# Shakey.net
KiCad netlist of a schematic drawn in EAGLE
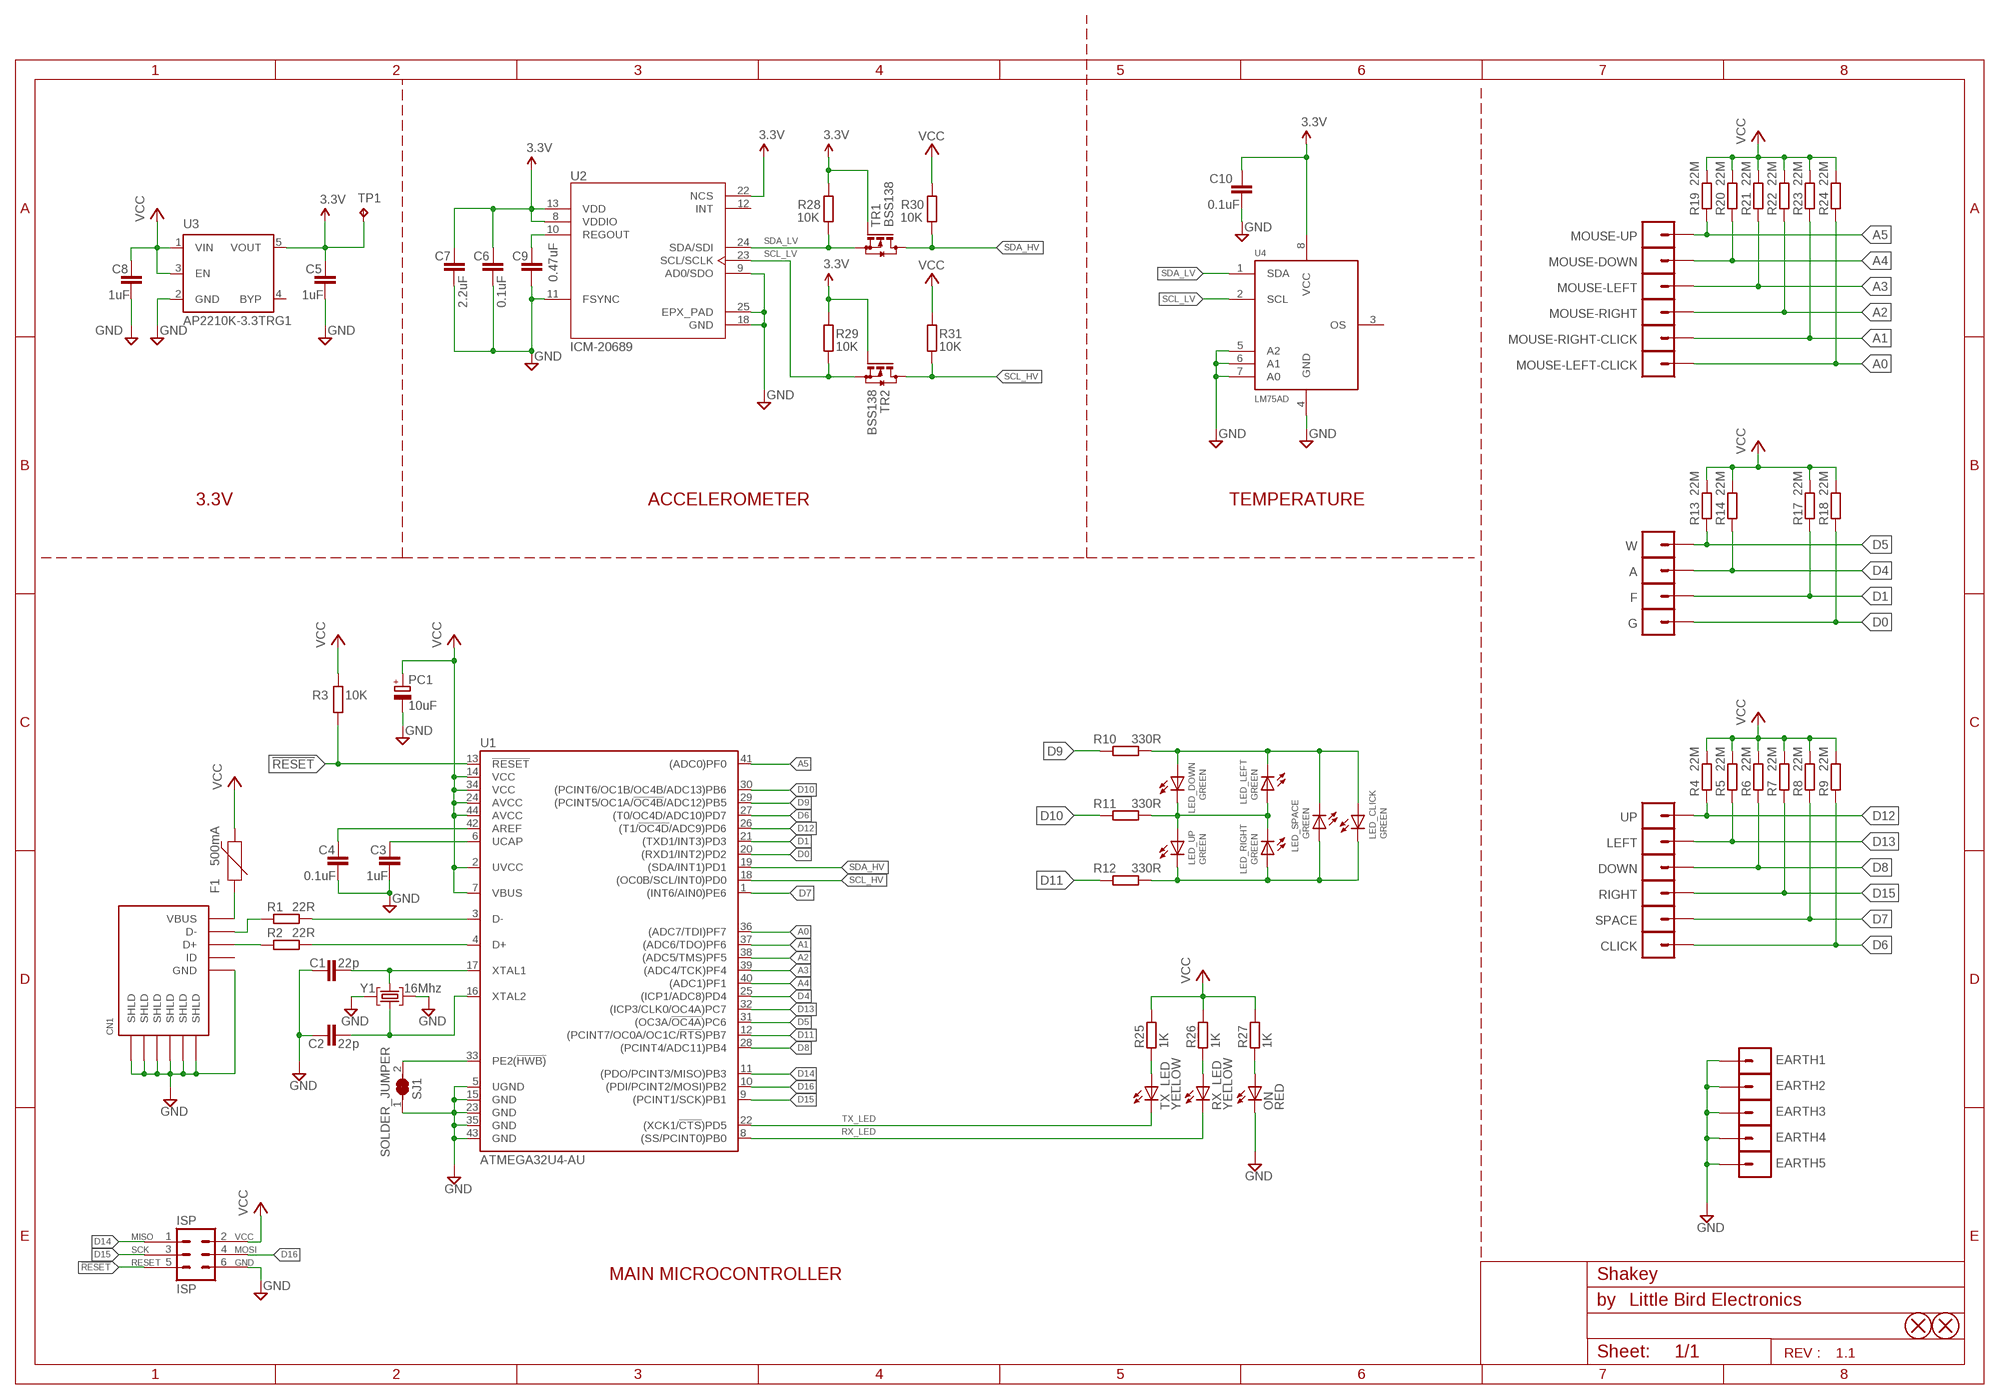
[diagram p0: schematic, sheet 1]

(export (version "E")
  (design (tool "Eeschema 10.0.6"))
  (components
    (comp (ref "A")
      (value "MA01-1-ALLIGATOR-3.0MM")
      (footprint "eagle-import:MA01-1-ALLIGATOR-3.0MM")
      (libsource (lib "eagle-import") (part "MA01-1-ALLIGATOR-3.0MM"))
    )
    (comp (ref "C1")
      (value "22p")
      (footprint "eagle-import:C0603")
      (description "CAP CER 22PF 16V C0G/NP0 0603")
      (fields (field (name "MF") "KEMET") (field (name "MPN") "C0603C220K4GACTU"))
      (libsource (lib "eagle-import") (part "C-EUC0603"))
    )
    (comp (ref "C2")
      (value "22p")
      (footprint "eagle-import:C0603")
      (description "CAP CER 22PF 16V C0G/NP0 0603")
      (fields (field (name "MF") "KEMET") (field (name "MPN") "C0603C220K4GACTU"))
      (libsource (lib "eagle-import") (part "C-EUC0603"))
    )
    (comp (ref "C3")
      (value "1uF")
      (footprint "eagle-import:C0603")
      (description "CAP CER 1UF 25V X5R 0603")
      (fields (field (name "MF") "Samsung Electro-Mechanics") (field (name "MPN") "CL10A105KA8NNNC"))
      (libsource (lib "eagle-import") (part "C-EUC0603"))
    )
    (comp (ref "C4")
      (value "0.1uF")
      (footprint "eagle-import:C0603")
      (description "CAP CER 0.1UF 50V X7R 0603")
      (fields (field (name "MF") "Samsung Electro-Mechanics") (field (name "MPN") "CL10B104KB8NNNC"))
      (libsource (lib "eagle-import") (part "C-EUC0603"))
    )
    (comp (ref "C5")
      (value "1uF")
      (footprint "eagle-import:C0603")
      (description "CAP CER 1UF 25V X5R 0603")
      (fields (field (name "MF") "Samsung Electro-Mechanics") (field (name "MPN") "CL10A105KA8NNNC"))
      (libsource (lib "eagle-import") (part "C-EUC0603"))
    )
    (comp (ref "C6")
      (value "0.1uF")
      (footprint "eagle-import:C0603")
      (description "CAP CER 0.1UF 50V X7R 0603")
      (fields (field (name "MF") "Samsung Electro-Mechanics") (field (name "MPN") "CL10B104KB8NNNC"))
      (libsource (lib "eagle-import") (part "C-EUC0603"))
    )
    (comp (ref "C7")
      (value "2.2uF")
      (footprint "eagle-import:C0603")
      (description "CAP CER 2.2UF 16V X5R 0603")
      (fields (field (name "MF") "Samsung Electro-Mechanics") (field (name "MPN") "CL10A225KO8NNNC"))
      (libsource (lib "eagle-import") (part "C-EUC0603"))
    )
    (comp (ref "C8")
      (value "1uF")
      (footprint "eagle-import:C0603")
      (description "CAP CER 1UF 25V X5R 0603")
      (fields (field (name "MF") "Samsung Electro-Mechanics") (field (name "MPN") "CL10A105KA8NNNC"))
      (libsource (lib "eagle-import") (part "C-EUC0603"))
    )
    (comp (ref "C9")
      (value "0.47uF")
      (footprint "eagle-import:C0603")
      (description "CAP CER 0.47UF 16V X7R 0603")
      (fields
        (field (name "MF") "Murata Electronics North America")
        (field (name "MPN") "GCM188R71C474KA55D")
      )
      (libsource (lib "eagle-import") (part "C-EUC0603"))
    )
    (comp (ref "C10")
      (value "0.1uF")
      (footprint "eagle-import:C0603")
      (description "CAP CER 0.1UF 50V X7R 0603")
      (fields (field (name "MF") "Samsung Electro-Mechanics") (field (name "MPN") "CL10B104KB8NNNC"))
      (libsource (lib "eagle-import") (part "C-EUC0603"))
    )
    (comp (ref "CLICK")
      (value "MA01-1-ALLIGATOR-3.0MM")
      (footprint "eagle-import:MA01-1-ALLIGATOR-3.0MM")
      (libsource (lib "eagle-import") (part "MA01-1-ALLIGATOR-3.0MM"))
    )
    (comp (ref "CN1")
      (value "MicroUSB")
      (footprint "eagle-import:4UCON-11071")
      (fields (field (name "MF") "4UCON") (field (name "MPN") "11071"))
      (libsource (lib "eagle-import") (part "CONN_USB-4UCON-11071"))
    )
    (comp (ref "DOWN")
      (value "MA01-1-ALLIGATOR-3.0MM")
      (footprint "eagle-import:MA01-1-ALLIGATOR-3.0MM")
      (libsource (lib "eagle-import") (part "MA01-1-ALLIGATOR-3.0MM"))
    )
    (comp (ref "EARTH1")
      (value "MA01-1-ALLIGATOR-3.0MM")
      (footprint "eagle-import:MA01-1-ALLIGATOR-3.0MM")
      (libsource (lib "eagle-import") (part "MA01-1-ALLIGATOR-3.0MM"))
    )
    (comp (ref "EARTH2")
      (value "MA01-1-ALLIGATOR-3.0MM")
      (footprint "eagle-import:MA01-1-ALLIGATOR-3.0MM")
      (libsource (lib "eagle-import") (part "MA01-1-ALLIGATOR-3.0MM"))
    )
    (comp (ref "EARTH3")
      (value "MA01-1-ALLIGATOR-3.0MM")
      (footprint "eagle-import:MA01-1-ALLIGATOR-3.0MM")
      (libsource (lib "eagle-import") (part "MA01-1-ALLIGATOR-3.0MM"))
    )
    (comp (ref "EARTH4")
      (value "MA01-1-ALLIGATOR-3.0MM")
      (footprint "eagle-import:MA01-1-ALLIGATOR-3.0MM")
      (libsource (lib "eagle-import") (part "MA01-1-ALLIGATOR-3.0MM"))
    )
    (comp (ref "EARTH5")
      (value "MA01-1-ALLIGATOR-3.0MM")
      (footprint "eagle-import:MA01-1-ALLIGATOR-3.0MM")
      (libsource (lib "eagle-import") (part "MA01-1-ALLIGATOR-3.0MM"))
    )
    (comp (ref "F")
      (value "MA01-1-ALLIGATOR-3.0MM")
      (footprint "eagle-import:MA01-1-ALLIGATOR-3.0MM")
      (libsource (lib "eagle-import") (part "MA01-1-ALLIGATOR-3.0MM"))
    )
    (comp (ref "F1")
      (value "500mA")
      (footprint "eagle-import:PPC-1206")
      (description "PTC RESET FUSE 8V 500MA 1206")
      (fields (field (name "MF") "Bel Fuse Inc.") (field (name "MPN") "0ZCJ0050FF2G"))
      (libsource (lib "eagle-import") (part "PPTC-1206"))
    )
    (comp (ref "G")
      (value "MA01-1-ALLIGATOR-3.0MM")
      (footprint "eagle-import:MA01-1-ALLIGATOR-3.0MM")
      (libsource (lib "eagle-import") (part "MA01-1-ALLIGATOR-3.0MM"))
    )
    (comp (ref "ISP")
      (value "ISP")
      (footprint "eagle-import:MA03-2")
      (libsource (lib "eagle-import") (part "DEBUGPORT-6PIN-ISP-AVR"))
    )
    (comp (ref "JP1")
      (value "FIDUCIAL-1X3MM")
      (footprint "eagle-import:FIDUCIAL-1X3MM")
      (libsource (lib "eagle-import") (part "FIDUCIAL-1X3MM"))
    )
    (comp (ref "JP2")
      (value "FIDUCIAL-1X3MM")
      (footprint "eagle-import:FIDUCIAL-1X3MM")
      (libsource (lib "eagle-import") (part "FIDUCIAL-1X3MM"))
    )
    (comp (ref "LED_CLICK")
      (value "GREEN")
      (footprint "eagle-import:LED-1206-LTST-BOTTOM")
      (description "LED GREEN CLEAR CHIP SMD")
      (fields (field (name "MF") "Lite-On Inc.") (field (name "MPN") "LTST-C230KGKT"))
      (libsource (lib "eagle-import") (part "LED-1206-LTST-BOTTOM"))
    )
    (comp (ref "LED_DOWN")
      (value "GREEN")
      (footprint "eagle-import:LED-1206-LTST-BOTTOM")
      (description "LED GREEN CLEAR CHIP SMD")
      (fields (field (name "MF") "Lite-On Inc.") (field (name "MPN") "LTST-C230KGKT"))
      (libsource (lib "eagle-import") (part "LED-1206-LTST-BOTTOM"))
    )
    (comp (ref "LED_LEFT")
      (value "GREEN")
      (footprint "eagle-import:LED-1206-LTST-BOTTOM")
      (description "LED GREEN CLEAR CHIP SMD")
      (fields (field (name "MF") "Lite-On Inc.") (field (name "MPN") "LTST-C230KGKT"))
      (libsource (lib "eagle-import") (part "LED-1206-LTST-BOTTOM"))
    )
    (comp (ref "LED_RIGHT")
      (value "GREEN")
      (footprint "eagle-import:LED-1206-LTST-BOTTOM")
      (description "LED GREEN CLEAR CHIP SMD")
      (fields (field (name "MF") "Lite-On Inc.") (field (name "MPN") "LTST-C230KGKT"))
      (libsource (lib "eagle-import") (part "LED-1206-LTST-BOTTOM"))
    )
    (comp (ref "LED_SPACE")
      (value "GREEN")
      (footprint "eagle-import:LED-1206-LTST-BOTTOM")
      (description "LED GREEN CLEAR CHIP SMD")
      (fields (field (name "MF") "Lite-On Inc.") (field (name "MPN") "LTST-C230KGKT"))
      (libsource (lib "eagle-import") (part "LED-1206-LTST-BOTTOM"))
    )
    (comp (ref "LED_UP")
      (value "GREEN")
      (footprint "eagle-import:LED-1206-LTST-BOTTOM")
      (description "LED GREEN CLEAR CHIP SMD")
      (fields (field (name "MF") "Lite-On Inc.") (field (name "MPN") "LTST-C230KGKT"))
      (libsource (lib "eagle-import") (part "LED-1206-LTST-BOTTOM"))
    )
    (comp (ref "LEFT")
      (value "MA01-1-ALLIGATOR-3.0MM")
      (footprint "eagle-import:MA01-1-ALLIGATOR-3.0MM")
      (libsource (lib "eagle-import") (part "MA01-1-ALLIGATOR-3.0MM"))
    )
    (comp (ref "MOUSE-DOWN")
      (value "MA01-1-ALLIGATOR-3.0MM")
      (footprint "eagle-import:MA01-1-ALLIGATOR-3.0MM")
      (libsource (lib "eagle-import") (part "MA01-1-ALLIGATOR-3.0MM"))
    )
    (comp (ref "MOUSE-LEFT")
      (value "MA01-1-ALLIGATOR-3.0MM")
      (footprint "eagle-import:MA01-1-ALLIGATOR-3.0MM")
      (libsource (lib "eagle-import") (part "MA01-1-ALLIGATOR-3.0MM"))
    )
    (comp (ref "MOUSE-LEFT-CLICK")
      (value "MA01-1-ALLIGATOR-3.0MM")
      (footprint "eagle-import:MA01-1-ALLIGATOR-3.0MM")
      (libsource (lib "eagle-import") (part "MA01-1-ALLIGATOR-3.0MM"))
    )
    (comp (ref "MOUSE-RIGHT")
      (value "MA01-1-ALLIGATOR-3.0MM")
      (footprint "eagle-import:MA01-1-ALLIGATOR-3.0MM")
      (libsource (lib "eagle-import") (part "MA01-1-ALLIGATOR-3.0MM"))
    )
    (comp (ref "MOUSE-RIGHT-CLICK")
      (value "MA01-1-ALLIGATOR-3.0MM")
      (footprint "eagle-import:MA01-1-ALLIGATOR-3.0MM")
      (libsource (lib "eagle-import") (part "MA01-1-ALLIGATOR-3.0MM"))
    )
    (comp (ref "MOUSE-UP")
      (value "MA01-1-ALLIGATOR-3.0MM")
      (footprint "eagle-import:MA01-1-ALLIGATOR-3.0MM")
      (libsource (lib "eagle-import") (part "MA01-1-ALLIGATOR-3.0MM"))
    )
    (comp (ref "ON")
      (value "RED")
      (footprint "eagle-import:LED-1206-LTST-BOTTOM")
      (description "LED RED CLEAR CHIP SMD")
      (fields (field (name "MF") "Lite-On Inc.") (field (name "MPN") "LTST-C230KRKT"))
      (libsource (lib "eagle-import") (part "LED-1206-LTST-BOTTOM"))
    )
    (comp (ref "PC1")
      (value "10uF")
      (footprint "eagle-import:CT6032")
      (description "CAP TANT 10UF 20V 10% 2312")
      (fields (field (name "MF") "KEMET") (field (name "MPN") "T491C106K020AT7280"))
      (libsource (lib "eagle-import") (part "CAP_POL-CT6032"))
    )
    (comp (ref "R1")
      (value "22R")
      (footprint "eagle-import:R0603")
      (description "RES 22 OHM 5% 1/10W 0603")
      (fields (field (name "MF") "Stackpole Electronics Inc.") (field (name "MPN") "RMCF0603JT22R0"))
      (libsource (lib "eagle-import") (part "R-EU_R0603"))
    )
    (comp (ref "R2")
      (value "22R")
      (footprint "eagle-import:R0603")
      (description "RES 22 OHM 5% 1/10W 0603")
      (fields (field (name "MF") "Stackpole Electronics Inc.") (field (name "MPN") "RMCF0603JT22R0"))
      (libsource (lib "eagle-import") (part "R-EU_R0603"))
    )
    (comp (ref "R3")
      (value "10K")
      (footprint "eagle-import:R0603")
      (description "RES 10K OHM 5% 1/10W 0603")
      (fields (field (name "MF") "Stackpole Electronics Inc.") (field (name "MPN") "RMCF0603JG10K0"))
      (libsource (lib "eagle-import") (part "R-EU_R0603"))
    )
    (comp (ref "R4")
      (value "22M")
      (footprint "eagle-import:R0603")
      (description "RES SMD 22M OHM 10% 1/10W 0603")
      (fields (field (name "MF") "Panasonic Electronic Components") (field (name "MPN") "ERJ-3GEYK226V"))
      (libsource (lib "eagle-import") (part "R-EU_R0603"))
    )
    (comp (ref "R5")
      (value "22M")
      (footprint "eagle-import:R0603")
      (description "RES SMD 22M OHM 10% 1/10W 0603")
      (fields (field (name "MF") "Panasonic Electronic Components") (field (name "MPN") "ERJ-3GEYK226V"))
      (libsource (lib "eagle-import") (part "R-EU_R0603"))
    )
    (comp (ref "R6")
      (value "22M")
      (footprint "eagle-import:R0603")
      (description "RES SMD 22M OHM 10% 1/10W 0603")
      (fields (field (name "MF") "Panasonic Electronic Components") (field (name "MPN") "ERJ-3GEYK226V"))
      (libsource (lib "eagle-import") (part "R-EU_R0603"))
    )
    (comp (ref "R7")
      (value "22M")
      (footprint "eagle-import:R0603")
      (description "RES SMD 22M OHM 10% 1/10W 0603")
      (fields (field (name "MF") "Panasonic Electronic Components") (field (name "MPN") "ERJ-3GEYK226V"))
      (libsource (lib "eagle-import") (part "R-EU_R0603"))
    )
    (comp (ref "R8")
      (value "22M")
      (footprint "eagle-import:R0603")
      (description "RES SMD 22M OHM 10% 1/10W 0603")
      (fields (field (name "MF") "Panasonic Electronic Components") (field (name "MPN") "ERJ-3GEYK226V"))
      (libsource (lib "eagle-import") (part "R-EU_R0603"))
    )
    (comp (ref "R9")
      (value "22M")
      (footprint "eagle-import:R0603")
      (description "RES SMD 22M OHM 10% 1/10W 0603")
      (fields (field (name "MF") "Panasonic Electronic Components") (field (name "MPN") "ERJ-3GEYK226V"))
      (libsource (lib "eagle-import") (part "R-EU_R0603"))
    )
    (comp (ref "R10")
      (value "330R")
      (footprint "eagle-import:R0603")
      (description "RES 330 OHM 5% 1/10W 0603")
      (fields (field (name "MF") "Stackpole Electronics Inc.") (field (name "MPN") "RMCF0603JT330R"))
      (libsource (lib "eagle-import") (part "R-EU_R0603"))
    )
    (comp (ref "R11")
      (value "330R")
      (footprint "eagle-import:R0603")
      (description "RES 330 OHM 5% 1/10W 0603")
      (fields (field (name "MF") "Stackpole Electronics Inc.") (field (name "MPN") "RMCF0603JT330R"))
      (libsource (lib "eagle-import") (part "R-EU_R0603"))
    )
    (comp (ref "R12")
      (value "330R")
      (footprint "eagle-import:R0603")
      (description "RES 330 OHM 5% 1/10W 0603")
      (fields (field (name "MF") "Stackpole Electronics Inc.") (field (name "MPN") "RMCF0603JT330R"))
      (libsource (lib "eagle-import") (part "R-EU_R0603"))
    )
    (comp (ref "R13")
      (value "22M")
      (footprint "eagle-import:R0603")
      (description "RES SMD 22M OHM 10% 1/10W 0603")
      (fields (field (name "MF") "Panasonic Electronic Components") (field (name "MPN") "ERJ-3GEYK226V"))
      (libsource (lib "eagle-import") (part "R-EU_R0603"))
    )
    (comp (ref "R14")
      (value "22M")
      (footprint "eagle-import:R0603")
      (description "RES SMD 22M OHM 10% 1/10W 0603")
      (fields (field (name "MF") "Panasonic Electronic Components") (field (name "MPN") "ERJ-3GEYK226V"))
      (libsource (lib "eagle-import") (part "R-EU_R0603"))
    )
    (comp (ref "R17")
      (value "22M")
      (footprint "eagle-import:R0603")
      (description "RES SMD 22M OHM 10% 1/10W 0603")
      (fields (field (name "MF") "Panasonic Electronic Components") (field (name "MPN") "ERJ-3GEYK226V"))
      (libsource (lib "eagle-import") (part "R-EU_R0603"))
    )
    (comp (ref "R18")
      (value "22M")
      (footprint "eagle-import:R0603")
      (description "RES SMD 22M OHM 10% 1/10W 0603")
      (fields (field (name "MF") "Panasonic Electronic Components") (field (name "MPN") "ERJ-3GEYK226V"))
      (libsource (lib "eagle-import") (part "R-EU_R0603"))
    )
    (comp (ref "R19")
      (value "22M")
      (footprint "eagle-import:R0603")
      (description "RES SMD 22M OHM 10% 1/10W 0603")
      (fields (field (name "MF") "Panasonic Electronic Components") (field (name "MPN") "ERJ-3GEYK226V"))
      (libsource (lib "eagle-import") (part "R-EU_R0603"))
    )
    (comp (ref "R20")
      (value "22M")
      (footprint "eagle-import:R0603")
      (description "RES SMD 22M OHM 10% 1/10W 0603")
      (fields (field (name "MF") "Panasonic Electronic Components") (field (name "MPN") "ERJ-3GEYK226V"))
      (libsource (lib "eagle-import") (part "R-EU_R0603"))
    )
    (comp (ref "R21")
      (value "22M")
      (footprint "eagle-import:R0603")
      (description "RES SMD 22M OHM 10% 1/10W 0603")
      (fields (field (name "MF") "Panasonic Electronic Components") (field (name "MPN") "ERJ-3GEYK226V"))
      (libsource (lib "eagle-import") (part "R-EU_R0603"))
    )
    (comp (ref "R22")
      (value "22M")
      (footprint "eagle-import:R0603")
      (description "RES SMD 22M OHM 10% 1/10W 0603")
      (fields (field (name "MF") "Panasonic Electronic Components") (field (name "MPN") "ERJ-3GEYK226V"))
      (libsource (lib "eagle-import") (part "R-EU_R0603"))
    )
    (comp (ref "R23")
      (value "22M")
      (footprint "eagle-import:R0603")
      (description "RES SMD 22M OHM 10% 1/10W 0603")
      (fields (field (name "MF") "Panasonic Electronic Components") (field (name "MPN") "ERJ-3GEYK226V"))
      (libsource (lib "eagle-import") (part "R-EU_R0603"))
    )
    (comp (ref "R24")
      (value "22M")
      (footprint "eagle-import:R0603")
      (description "RES SMD 22M OHM 10% 1/10W 0603")
      (fields (field (name "MF") "Panasonic Electronic Components") (field (name "MPN") "ERJ-3GEYK226V"))
      (libsource (lib "eagle-import") (part "R-EU_R0603"))
    )
    (comp (ref "R25")
      (value "1K")
      (footprint "eagle-import:R0603")
      (description "RES SMD 1K OHM 5% 1/10W 0603")
      (fields (field (name "MF") "Yageo") (field (name "MPN") "RC0603JR-071KL"))
      (libsource (lib "eagle-import") (part "R-EU_R0603"))
    )
    (comp (ref "R26")
      (value "1K")
      (footprint "eagle-import:R0603")
      (description "RES SMD 1K OHM 5% 1/10W 0603")
      (fields (field (name "MF") "Yageo") (field (name "MPN") "RC0603JR-071KL"))
      (libsource (lib "eagle-import") (part "R-EU_R0603"))
    )
    (comp (ref "R27")
      (value "1K")
      (footprint "eagle-import:R0603")
      (description "RES SMD 1K OHM 5% 1/10W 0603")
      (fields (field (name "MF") "Yageo") (field (name "MPN") "RC0603JR-071KL"))
      (libsource (lib "eagle-import") (part "R-EU_R0603"))
    )
    (comp (ref "R28")
      (value "10K")
      (footprint "eagle-import:R0603")
      (description "RES 10K OHM 5% 1/10W 0603")
      (fields (field (name "MF") "Stackpole Electronics Inc.") (field (name "MPN") "RMCF0603JG10K0"))
      (libsource (lib "eagle-import") (part "R-EU_R0603"))
    )
    (comp (ref "R29")
      (value "10K")
      (footprint "eagle-import:R0603")
      (description "RES 10K OHM 5% 1/10W 0603")
      (fields (field (name "MF") "Stackpole Electronics Inc.") (field (name "MPN") "RMCF0603JG10K0"))
      (libsource (lib "eagle-import") (part "R-EU_R0603"))
    )
    (comp (ref "R30")
      (value "10K")
      (footprint "eagle-import:R0603")
      (description "RES 10K OHM 5% 1/10W 0603")
      (fields (field (name "MF") "Stackpole Electronics Inc.") (field (name "MPN") "RMCF0603JG10K0"))
      (libsource (lib "eagle-import") (part "R-EU_R0603"))
    )
    (comp (ref "R31")
      (value "10K")
      (footprint "eagle-import:R0603")
      (description "RES 10K OHM 5% 1/10W 0603")
      (fields (field (name "MF") "Stackpole Electronics Inc.") (field (name "MPN") "RMCF0603JG10K0"))
      (libsource (lib "eagle-import") (part "R-EU_R0603"))
    )
    (comp (ref "RIGHT")
      (value "MA01-1-ALLIGATOR-3.0MM")
      (footprint "eagle-import:MA01-1-ALLIGATOR-3.0MM")
      (libsource (lib "eagle-import") (part "MA01-1-ALLIGATOR-3.0MM"))
    )
    (comp (ref "RX_LED")
      (value "YELLOW")
      (footprint "eagle-import:LED-1206-LTST-BOTTOM")
      (description "LED YELLOW CLEAR CHIP SMD")
      (fields (field (name "MF") "Lite-On Inc.") (field (name "MPN") "LTST-C230KSKT"))
      (libsource (lib "eagle-import") (part "LED-1206-LTST-BOTTOM"))
    )
    (comp (ref "SJ1")
      (value "SOLDER_JUMPER")
      (footprint "eagle-import:SOLDER_JUMPER_NC")
      (libsource (lib "eagle-import") (part "SOLDER_JUMPER_NC"))
    )
    (comp (ref "SPACE")
      (value "MA01-1-ALLIGATOR-3.0MM")
      (footprint "eagle-import:MA01-1-ALLIGATOR-3.0MM")
      (libsource (lib "eagle-import") (part "MA01-1-ALLIGATOR-3.0MM"))
    )
    (comp (ref "TP1")
      (value "TESTPAD")
      (footprint "eagle-import:TP-2.54MM")
      (libsource (lib "eagle-import") (part "TESTPAD-2.54MM"))
    )
    (comp (ref "TR1")
      (value "BSS138")
      (footprint "eagle-import:SOT23")
      (description "MOSFET N-CH 50V 220MA SOT-23")
      (fields (field (name "MF") "ON Semiconductor"))
      (libsource (lib "eagle-import") (part "MOSFET-N-BSS138"))
    )
    (comp (ref "TR2")
      (value "BSS138")
      (footprint "eagle-import:SOT23")
      (description "MOSFET N-CH 50V 220MA SOT-23")
      (fields (field (name "MF") "ON Semiconductor"))
      (libsource (lib "eagle-import") (part "MOSFET-N-BSS138"))
    )
    (comp (ref "TX_LED")
      (value "YELLOW")
      (footprint "eagle-import:LED-1206-LTST-BOTTOM")
      (description "LED YELLOW CLEAR CHIP SMD")
      (fields (field (name "MF") "Lite-On Inc.") (field (name "MPN") "LTST-C230KSKT"))
      (libsource (lib "eagle-import") (part "LED-1206-LTST-BOTTOM"))
    )
    (comp (ref "U1")
      (value "ATMEGA32U4-AU")
      (footprint "eagle-import:TQFP44")
      (fields (field (name "MF") "Microchip Technology"))
      (libsource (lib "eagle-import") (part "ATMEGA32U4-AU"))
    )
    (comp (ref "U2")
      (value "ICM-20689")
      (footprint "eagle-import:QFN-24-4X4-0.9MM")
      (description "IMU ACCEL/GYRO/TEMP I2C/SPI QFN")
      (fields (field (name "MF") "TDK InvenSense"))
      (libsource (lib "eagle-import") (part "ICM-20689"))
    )
    (comp (ref "U3")
      (value "AP2210K-3.3TRG1")
      (footprint "eagle-import:SOT23-5")
      (fields (field (name "MF") "Diodes Inc"))
      (libsource (lib "eagle-import") (part "AP2210K-3.3TRG1"))
    )
    (comp (ref "U4")
      (value "LM75AD")
      (footprint "eagle-import:SOT96-1")
      (description "SENSOR DIGITAL -55C-125C 8SO")
      (fields (field (name "MF") "NXP USA Inc.") (field (name "MPN") "LM75AD,118"))
      (libsource (lib "eagle-import") (part "LM75AD"))
    )
    (comp (ref "UP")
      (value "MA01-1-ALLIGATOR-3.0MM")
      (footprint "eagle-import:MA01-1-ALLIGATOR-3.0MM")
      (libsource (lib "eagle-import") (part "MA01-1-ALLIGATOR-3.0MM"))
    )
    (comp (ref "W")
      (value "MA01-1-ALLIGATOR-3.0MM")
      (footprint "eagle-import:MA01-1-ALLIGATOR-3.0MM")
      (libsource (lib "eagle-import") (part "MA01-1-ALLIGATOR-3.0MM"))
    )
    (comp (ref "Y1")
      (value "16Mhz")
      (footprint "eagle-import:FA-238")
      (description "CRYSTAL 16.0000MHZ 18PF SMD")
      (fields (field (name "MF") "EPSON") (field (name "MPN") "FA-238 16.0000MB-C3"))
      (libsource (lib "eagle-import") (part "CRYSTAL_GROUNDED_2GND-FA-238"))
    )
  )
  (nets
    (net (code "1") (name "/RX_LED") (class "Default")
      (node (ref "RX_LED") (pin "C") (pinfunction "C_C") (pintype "passive"))
      (node (ref "U1") (pin "8") (pinfunction "(SS/PCINT0)PB0_8") (pintype "bidirectional"))
    )
    (net (code "2") (name "/TX_LED") (class "Default")
      (node (ref "TX_LED") (pin "C") (pinfunction "C_C") (pintype "passive"))
      (node (ref "U1") (pin "22") (pinfunction "(XCK1/~{CTS})PD5_22") (pintype "bidirectional"))
    )
    (net (code "3") (name "/~{RESET}") (class "Default")
      (node (ref "ISP") (pin "5") (pinfunction "5_5") (pintype "passive"))
      (node (ref "R3") (pin "1") (pinfunction "1_1") (pintype "passive"))
      (node (ref "U1") (pin "13") (pinfunction "~{RESET}_13") (pintype "bidirectional"))
    )
    (net (code "4") (name "3.3V") (class "Default")
      (node (ref "C10") (pin "2") (pinfunction "2_2") (pintype "passive"))
      (node (ref "C5") (pin "2") (pinfunction "2_2") (pintype "passive"))
      (node (ref "C6") (pin "2") (pinfunction "2_2") (pintype "passive"))
      (node (ref "C7") (pin "2") (pinfunction "2_2") (pintype "passive"))
      (node (ref "R28") (pin "2") (pinfunction "2_2") (pintype "passive"))
      (node (ref "R29") (pin "2") (pinfunction "2_2") (pintype "passive"))
      (node (ref "TP1") (pin "TP") (pinfunction "TP_TP") (pintype "input"))
      (node (ref "TR1") (pin "1") (pinfunction "G_1") (pintype "passive"))
      (node (ref "TR2") (pin "1") (pinfunction "G_1") (pintype "passive"))
      (node (ref "U2") (pin "13") (pinfunction "VDD_13") (pintype "power_in"))
      (node (ref "U2") (pin "22") (pinfunction "NCS_22") (pintype "input"))
      (node (ref "U2") (pin "8") (pinfunction "VDDIO_8") (pintype "power_in"))
      (node (ref "U3") (pin "5") (pinfunction "VOUT_5") (pintype "passive"))
      (node (ref "U4") (pin "8") (pinfunction "VCC_8") (pintype "bidirectional"))
    )
    (net (code "5") (name "A0") (class "Default")
      (node (ref "MOUSE-LEFT-CLICK") (pin "1@0") (pinfunction "1_1@0") (pintype "passive"))
      (node (ref "MOUSE-LEFT-CLICK") (pin "1@1") (pinfunction "1_1@1") (pintype "passive"))
      (node (ref "R24") (pin "1") (pinfunction "1_1") (pintype "passive"))
      (node (ref "U1") (pin "36") (pinfunction "(ADC7/TDI)PF7_36") (pintype "bidirectional"))
    )
    (net (code "6") (name "A1") (class "Default")
      (node (ref "MOUSE-RIGHT-CLICK") (pin "1@0") (pinfunction "1_1@0") (pintype "passive"))
      (node (ref "MOUSE-RIGHT-CLICK") (pin "1@1") (pinfunction "1_1@1") (pintype "passive"))
      (node (ref "R23") (pin "1") (pinfunction "1_1") (pintype "passive"))
      (node (ref "U1") (pin "37") (pinfunction "(ADC6/TDO)PF6_37") (pintype "bidirectional"))
    )
    (net (code "7") (name "A2") (class "Default")
      (node (ref "MOUSE-RIGHT") (pin "1@0") (pinfunction "1_1@0") (pintype "passive"))
      (node (ref "MOUSE-RIGHT") (pin "1@1") (pinfunction "1_1@1") (pintype "passive"))
      (node (ref "R22") (pin "1") (pinfunction "1_1") (pintype "passive"))
      (node (ref "U1") (pin "38") (pinfunction "(ADC5/TMS)PF5_38") (pintype "bidirectional"))
    )
    (net (code "8") (name "A3") (class "Default")
      (node (ref "MOUSE-LEFT") (pin "1@0") (pinfunction "1_1@0") (pintype "passive"))
      (node (ref "MOUSE-LEFT") (pin "1@1") (pinfunction "1_1@1") (pintype "passive"))
      (node (ref "R21") (pin "1") (pinfunction "1_1") (pintype "passive"))
      (node (ref "U1") (pin "39") (pinfunction "(ADC4/TCK)PF4_39") (pintype "bidirectional"))
    )
    (net (code "9") (name "A4") (class "Default")
      (node (ref "MOUSE-DOWN") (pin "1@0") (pinfunction "1_1@0") (pintype "passive"))
      (node (ref "MOUSE-DOWN") (pin "1@1") (pinfunction "1_1@1") (pintype "passive"))
      (node (ref "R20") (pin "1") (pinfunction "1_1") (pintype "passive"))
      (node (ref "U1") (pin "40") (pinfunction "(ADC1)PF1_40") (pintype "bidirectional"))
    )
    (net (code "10") (name "A5") (class "Default")
      (node (ref "MOUSE-UP") (pin "1@0") (pinfunction "1_1@0") (pintype "passive"))
      (node (ref "MOUSE-UP") (pin "1@1") (pinfunction "1_1@1") (pintype "passive"))
      (node (ref "R19") (pin "1") (pinfunction "1_1") (pintype "passive"))
      (node (ref "U1") (pin "41") (pinfunction "(ADC0)PF0_41") (pintype "bidirectional"))
    )
    (net (code "11") (name "D0") (class "Default")
      (node (ref "G") (pin "1@0") (pinfunction "1_1@0") (pintype "passive"))
      (node (ref "G") (pin "1@1") (pinfunction "1_1@1") (pintype "passive"))
      (node (ref "R18") (pin "1") (pinfunction "1_1") (pintype "passive"))
      (node (ref "U1") (pin "20") (pinfunction "(RXD1/INT2)PD2_20") (pintype "bidirectional"))
    )
    (net (code "12") (name "D1") (class "Default")
      (node (ref "F") (pin "1@0") (pinfunction "1_1@0") (pintype "passive"))
      (node (ref "F") (pin "1@1") (pinfunction "1_1@1") (pintype "passive"))
      (node (ref "R17") (pin "1") (pinfunction "1_1") (pintype "passive"))
      (node (ref "U1") (pin "21") (pinfunction "(TXD1/INT3)PD3_21") (pintype "bidirectional"))
    )
    (net (code "13") (name "D4") (class "Default")
      (node (ref "A") (pin "1@0") (pinfunction "1_1@0") (pintype "passive"))
      (node (ref "A") (pin "1@1") (pinfunction "1_1@1") (pintype "passive"))
      (node (ref "R14") (pin "1") (pinfunction "1_1") (pintype "passive"))
      (node (ref "U1") (pin "25") (pinfunction "(ICP1/ADC8)PD4_25") (pintype "bidirectional"))
    )
    (net (code "14") (name "D5") (class "Default")
      (node (ref "R13") (pin "1") (pinfunction "1_1") (pintype "passive"))
      (node (ref "U1") (pin "31") (pinfunction "(OC3A/~{OC4A})PC6_31") (pintype "bidirectional"))
      (node (ref "W") (pin "1@0") (pinfunction "1_1@0") (pintype "passive"))
      (node (ref "W") (pin "1@1") (pinfunction "1_1@1") (pintype "passive"))
    )
    (net (code "15") (name "D6") (class "Default")
      (node (ref "CLICK") (pin "1@0") (pinfunction "1_1@0") (pintype "passive"))
      (node (ref "CLICK") (pin "1@1") (pinfunction "1_1@1") (pintype "passive"))
      (node (ref "R9") (pin "1") (pinfunction "1_1") (pintype "passive"))
      (node (ref "U1") (pin "27") (pinfunction "(T0/OC4D/ADC10)PD7_27") (pintype "bidirectional"))
    )
    (net (code "16") (name "D7") (class "Default")
      (node (ref "R8") (pin "1") (pinfunction "1_1") (pintype "passive"))
      (node (ref "SPACE") (pin "1@0") (pinfunction "1_1@0") (pintype "passive"))
      (node (ref "SPACE") (pin "1@1") (pinfunction "1_1@1") (pintype "passive"))
      (node (ref "U1") (pin "1") (pinfunction "(INT6/AIN0)PE6_1") (pintype "bidirectional"))
    )
    (net (code "17") (name "D8") (class "Default")
      (node (ref "DOWN") (pin "1@0") (pinfunction "1_1@0") (pintype "passive"))
      (node (ref "DOWN") (pin "1@1") (pinfunction "1_1@1") (pintype "passive"))
      (node (ref "R6") (pin "1") (pinfunction "1_1") (pintype "passive"))
      (node (ref "U1") (pin "28") (pinfunction "(PCINT4/ADC11)PB4_28") (pintype "bidirectional"))
    )
    (net (code "18") (name "D9") (class "Default")
      (node (ref "R10") (pin "1") (pinfunction "1_1") (pintype "passive"))
      (node (ref "U1") (pin "29") (pinfunction "(PCINT5/OC1A/~{OC4B}/ADC12)PB5_29") (pintype "bidirectional"))
    )
    (net (code "19") (name "D10") (class "Default")
      (node (ref "R11") (pin "1") (pinfunction "1_1") (pintype "passive"))
      (node (ref "U1") (pin "30") (pinfunction "(PCINT6/OC1B/OC4B/ADC13)PB6_30") (pintype "bidirectional"))
    )
    (net (code "20") (name "D11") (class "Default")
      (node (ref "R12") (pin "1") (pinfunction "1_1") (pintype "passive"))
      (node (ref "U1") (pin "12") (pinfunction "(PCINT7/OC0A/OC1C/~{RTS})PB7_12") (pintype "bidirectional"))
    )
    (net (code "21") (name "D12") (class "Default")
      (node (ref "R4") (pin "1") (pinfunction "1_1") (pintype "passive"))
      (node (ref "U1") (pin "26") (pinfunction "(T1/~{OC4D}/ADC9)PD6_26") (pintype "bidirectional"))
      (node (ref "UP") (pin "1@0") (pinfunction "1_1@0") (pintype "passive"))
      (node (ref "UP") (pin "1@1") (pinfunction "1_1@1") (pintype "passive"))
    )
    (net (code "22") (name "D13") (class "Default")
      (node (ref "LEFT") (pin "1@0") (pinfunction "1_1@0") (pintype "passive"))
      (node (ref "LEFT") (pin "1@1") (pinfunction "1_1@1") (pintype "passive"))
      (node (ref "R5") (pin "1") (pinfunction "1_1") (pintype "passive"))
      (node (ref "U1") (pin "32") (pinfunction "(ICP3/CLK0/OC4A)PC7_32") (pintype "bidirectional"))
    )
    (net (code "23") (name "D14") (class "Default")
      (node (ref "ISP") (pin "1") (pinfunction "1_1") (pintype "passive"))
      (node (ref "U1") (pin "11") (pinfunction "(PDO/PCINT3/MISO)PB3_11") (pintype "bidirectional"))
    )
    (net (code "24") (name "D15") (class "Default")
      (node (ref "ISP") (pin "3") (pinfunction "3_3") (pintype "passive"))
      (node (ref "R7") (pin "1") (pinfunction "1_1") (pintype "passive"))
      (node (ref "RIGHT") (pin "1@0") (pinfunction "1_1@0") (pintype "passive"))
      (node (ref "RIGHT") (pin "1@1") (pinfunction "1_1@1") (pintype "passive"))
      (node (ref "U1") (pin "9") (pinfunction "(PCINT1/SCK)PB1_9") (pintype "bidirectional"))
    )
    (net (code "25") (name "D16") (class "Default")
      (node (ref "ISP") (pin "4") (pinfunction "4_4") (pintype "passive"))
      (node (ref "U1") (pin "10") (pinfunction "(PDI/PCINT2/MOSI)PB2_10") (pintype "bidirectional"))
    )
    (net (code "26") (name "GND") (class "Default")
      (node (ref "C1") (pin "1") (pinfunction "1_1") (pintype "passive"))
      (node (ref "C10") (pin "1") (pinfunction "1_1") (pintype "passive"))
      (node (ref "C2") (pin "1") (pinfunction "1_1") (pintype "passive"))
      (node (ref "C3") (pin "1") (pinfunction "1_1") (pintype "passive"))
      (node (ref "C4") (pin "1") (pinfunction "1_1") (pintype "passive"))
      (node (ref "C5") (pin "1") (pinfunction "1_1") (pintype "passive"))
      (node (ref "C6") (pin "1") (pinfunction "1_1") (pintype "passive"))
      (node (ref "C7") (pin "1") (pinfunction "1_1") (pintype "passive"))
      (node (ref "C8") (pin "1") (pinfunction "1_1") (pintype "passive"))
      (node (ref "C9") (pin "1") (pinfunction "1_1") (pintype "passive"))
      (node (ref "CN1") (pin "GND") (pinfunction "GND_GND") (pintype "power_in"))
      (node (ref "CN1") (pin "SHLD@1") (pinfunction "SHLD_SHLD@1") (pintype "passive"))
      (node (ref "CN1") (pin "SHLD@2") (pinfunction "SHLD_SHLD@2") (pintype "passive"))
      (node (ref "CN1") (pin "SHLD@3") (pinfunction "SHLD_SHLD@3") (pintype "passive"))
      (node (ref "CN1") (pin "SHLD@4") (pinfunction "SHLD_SHLD@4") (pintype "passive"))
      (node (ref "CN1") (pin "SHLD@5") (pinfunction "SHLD_SHLD@5") (pintype "passive"))
      (node (ref "CN1") (pin "SHLD@6") (pinfunction "SHLD_SHLD@6") (pintype "passive"))
      (node (ref "EARTH1") (pin "1@0") (pinfunction "1_1@0") (pintype "passive"))
      (node (ref "EARTH1") (pin "1@1") (pinfunction "1_1@1") (pintype "passive"))
      (node (ref "EARTH2") (pin "1@0") (pinfunction "1_1@0") (pintype "passive"))
      (node (ref "EARTH2") (pin "1@1") (pinfunction "1_1@1") (pintype "passive"))
      (node (ref "EARTH3") (pin "1@0") (pinfunction "1_1@0") (pintype "passive"))
      (node (ref "EARTH3") (pin "1@1") (pinfunction "1_1@1") (pintype "passive"))
      (node (ref "EARTH4") (pin "1@0") (pinfunction "1_1@0") (pintype "passive"))
      (node (ref "EARTH4") (pin "1@1") (pinfunction "1_1@1") (pintype "passive"))
      (node (ref "EARTH5") (pin "1@0") (pinfunction "1_1@0") (pintype "passive"))
      (node (ref "EARTH5") (pin "1@1") (pinfunction "1_1@1") (pintype "passive"))
      (node (ref "ISP") (pin "6") (pinfunction "6_6") (pintype "passive"))
      (node (ref "ON") (pin "C") (pinfunction "C_C") (pintype "passive"))
      (node (ref "PC1") (pin "-") (pinfunction "-_-") (pintype "passive"))
      (node (ref "SJ1") (pin "1") (pinfunction "1_1") (pintype "passive"))
      (node (ref "U1") (pin "15") (pinfunction "GND_15") (pintype "bidirectional"))
      (node (ref "U1") (pin "23") (pinfunction "GND_23") (pintype "bidirectional"))
      (node (ref "U1") (pin "35") (pinfunction "GND_35") (pintype "bidirectional"))
      (node (ref "U1") (pin "43") (pinfunction "GND_43") (pintype "bidirectional"))
      (node (ref "U1") (pin "5") (pinfunction "UGND_5") (pintype "bidirectional"))
      (node (ref "U2") (pin "11") (pinfunction "FSYNC_11") (pintype "input"))
      (node (ref "U2") (pin "18") (pinfunction "GND_18") (pintype "power_in"))
      (node (ref "U2") (pin "25") (pinfunction "EPX_PAD_25") (pintype "power_in"))
      (node (ref "U2") (pin "9") (pinfunction "AD0/SDO_9") (pintype "bidirectional"))
      (node (ref "U3") (pin "2") (pinfunction "GND_2") (pintype "power_in"))
      (node (ref "U4") (pin "4") (pinfunction "GND_4") (pintype "bidirectional"))
      (node (ref "U4") (pin "5") (pinfunction "A2_5") (pintype "bidirectional"))
      (node (ref "U4") (pin "6") (pinfunction "A1_6") (pintype "bidirectional"))
      (node (ref "U4") (pin "7") (pinfunction "A0_7") (pintype "bidirectional"))
      (node (ref "Y1") (pin "2") (pinfunction "2_2") (pintype "passive"))
      (node (ref "Y1") (pin "4") (pinfunction "4_4") (pintype "passive"))
    )
    (net (code "27") (name "Net-(CN1-PadD+)") (class "Default")
      (node (ref "CN1") (pin "D+") (pinfunction "D+_D+") (pintype "bidirectional"))
      (node (ref "R2") (pin "1") (pinfunction "1_1") (pintype "passive"))
    )
    (net (code "28") (name "Net-(CN1-PadD-)") (class "Default")
      (node (ref "CN1") (pin "D-") (pinfunction "D-_D-") (pintype "bidirectional"))
      (node (ref "R1") (pin "1") (pinfunction "1_1") (pintype "passive"))
    )
    (net (code "29") (name "Net-(CN1-PadVBUS)") (class "Default")
      (node (ref "CN1") (pin "VBUS") (pinfunction "VBUS_VBUS") (pintype "bidirectional"))
      (node (ref "F1") (pin "1") (pinfunction "1_1") (pintype "bidirectional"))
    )
    (net (code "30") (name "Net-(LED_CLICK-PadA)") (class "Default")
      (node (ref "LED_CLICK") (pin "A") (pinfunction "A_A") (pintype "passive"))
      (node (ref "LED_DOWN") (pin "A") (pinfunction "A_A") (pintype "passive"))
      (node (ref "LED_LEFT") (pin "C") (pinfunction "C_C") (pintype "passive"))
      (node (ref "LED_SPACE") (pin "C") (pinfunction "C_C") (pintype "passive"))
      (node (ref "R10") (pin "2") (pinfunction "2_2") (pintype "passive"))
    )
    (net (code "31") (name "Net-(LED_CLICK-PadC)") (class "Default")
      (node (ref "LED_CLICK") (pin "C") (pinfunction "C_C") (pintype "passive"))
      (node (ref "LED_RIGHT") (pin "A") (pinfunction "A_A") (pintype "passive"))
      (node (ref "LED_SPACE") (pin "A") (pinfunction "A_A") (pintype "passive"))
      (node (ref "LED_UP") (pin "C") (pinfunction "C_C") (pintype "passive"))
      (node (ref "R12") (pin "2") (pinfunction "2_2") (pintype "passive"))
    )
    (net (code "32") (name "Net-(LED_DOWN-PadC)") (class "Default")
      (node (ref "LED_DOWN") (pin "C") (pinfunction "C_C") (pintype "passive"))
      (node (ref "LED_LEFT") (pin "A") (pinfunction "A_A") (pintype "passive"))
      (node (ref "LED_RIGHT") (pin "C") (pinfunction "C_C") (pintype "passive"))
      (node (ref "LED_UP") (pin "A") (pinfunction "A_A") (pintype "passive"))
      (node (ref "R11") (pin "2") (pinfunction "2_2") (pintype "passive"))
    )
    (net (code "33") (name "Net-(ON-PadA)") (class "Default")
      (node (ref "ON") (pin "A") (pinfunction "A_A") (pintype "passive"))
      (node (ref "R27") (pin "1") (pinfunction "1_1") (pintype "passive"))
    )
    (net (code "34") (name "Net-(R25-Pad1)") (class "Default")
      (node (ref "R25") (pin "1") (pinfunction "1_1") (pintype "passive"))
      (node (ref "TX_LED") (pin "A") (pinfunction "A_A") (pintype "passive"))
    )
    (net (code "35") (name "Net-(R26-Pad1)") (class "Default")
      (node (ref "R26") (pin "1") (pinfunction "1_1") (pintype "passive"))
      (node (ref "RX_LED") (pin "A") (pinfunction "A_A") (pintype "passive"))
    )
    (net (code "36") (name "Net-(U1-AREF)") (class "Default")
      (node (ref "C4") (pin "2") (pinfunction "2_2") (pintype "passive"))
      (node (ref "U1") (pin "42") (pinfunction "AREF_42") (pintype "bidirectional"))
    )
    (net (code "37") (name "Net-(U1-D+)") (class "Default")
      (node (ref "R2") (pin "2") (pinfunction "2_2") (pintype "passive"))
      (node (ref "U1") (pin "4") (pinfunction "D+_4") (pintype "bidirectional"))
    )
    (net (code "38") (name "Net-(U1-D-)") (class "Default")
      (node (ref "R1") (pin "2") (pinfunction "2_2") (pintype "passive"))
      (node (ref "U1") (pin "3") (pinfunction "D-_3") (pintype "bidirectional"))
    )
    (net (code "39") (name "Net-(U1-PE2(~{HWB}))") (class "Default")
      (node (ref "SJ1") (pin "2") (pinfunction "2_2") (pintype "passive"))
      (node (ref "U1") (pin "33") (pinfunction "PE2(~{HWB})_33") (pintype "bidirectional"))
    )
    (net (code "40") (name "Net-(U1-UCAP)") (class "Default")
      (node (ref "C3") (pin "2") (pinfunction "2_2") (pintype "passive"))
      (node (ref "U1") (pin "6") (pinfunction "UCAP_6") (pintype "bidirectional"))
    )
    (net (code "41") (name "Net-(U1-XTAL1)") (class "Default")
      (node (ref "C1") (pin "2") (pinfunction "2_2") (pintype "passive"))
      (node (ref "U1") (pin "17") (pinfunction "XTAL1_17") (pintype "bidirectional"))
      (node (ref "Y1") (pin "1") (pinfunction "1_1") (pintype "passive"))
    )
    (net (code "42") (name "Net-(U1-XTAL2)") (class "Default")
      (node (ref "C2") (pin "2") (pinfunction "2_2") (pintype "passive"))
      (node (ref "U1") (pin "16") (pinfunction "XTAL2_16") (pintype "bidirectional"))
      (node (ref "Y1") (pin "3") (pinfunction "3_3") (pintype "passive"))
    )
    (net (code "43") (name "Net-(U2-REGOUT)") (class "Default")
      (node (ref "C9") (pin "2") (pinfunction "2_2") (pintype "passive"))
      (node (ref "U2") (pin "10") (pinfunction "REGOUT_10") (pintype "output"))
    )
    (net (code "44") (name "SCL_HV") (class "Default")
      (node (ref "R31") (pin "1") (pinfunction "1_1") (pintype "passive"))
      (node (ref "TR2") (pin "3") (pinfunction "D_3") (pintype "passive"))
      (node (ref "U1") (pin "18") (pinfunction "(OC0B/SCL/INT0)PD0_18") (pintype "bidirectional"))
    )
    (net (code "45") (name "SCL_LV") (class "Default")
      (node (ref "R29") (pin "1") (pinfunction "1_1") (pintype "passive"))
      (node (ref "TR2") (pin "2") (pinfunction "S_2") (pintype "passive"))
      (node (ref "U2") (pin "23") (pinfunction "SCL/SCLK_23") (pintype "input"))
      (node (ref "U4") (pin "2") (pinfunction "SCL_2") (pintype "bidirectional"))
    )
    (net (code "46") (name "SDA_HV") (class "Default")
      (node (ref "R30") (pin "1") (pinfunction "1_1") (pintype "passive"))
      (node (ref "TR1") (pin "3") (pinfunction "D_3") (pintype "passive"))
      (node (ref "U1") (pin "19") (pinfunction "(SDA/INT1)PD1_19") (pintype "bidirectional"))
    )
    (net (code "47") (name "SDA_LV") (class "Default")
      (node (ref "R28") (pin "1") (pinfunction "1_1") (pintype "passive"))
      (node (ref "TR1") (pin "2") (pinfunction "S_2") (pintype "passive"))
      (node (ref "U2") (pin "24") (pinfunction "SDA/SDI_24") (pintype "bidirectional"))
      (node (ref "U4") (pin "1") (pinfunction "SDA_1") (pintype "bidirectional"))
    )
    (net (code "48") (name "VCC") (class "Default")
      (node (ref "C8") (pin "2") (pinfunction "2_2") (pintype "passive"))
      (node (ref "F1") (pin "2") (pinfunction "2_2") (pintype "bidirectional"))
      (node (ref "ISP") (pin "2") (pinfunction "2_2") (pintype "passive"))
      (node (ref "PC1") (pin "+") (pinfunction "+_+") (pintype "passive"))
      (node (ref "R13") (pin "2") (pinfunction "2_2") (pintype "passive"))
      (node (ref "R14") (pin "2") (pinfunction "2_2") (pintype "passive"))
      (node (ref "R17") (pin "2") (pinfunction "2_2") (pintype "passive"))
      (node (ref "R18") (pin "2") (pinfunction "2_2") (pintype "passive"))
      (node (ref "R19") (pin "2") (pinfunction "2_2") (pintype "passive"))
      (node (ref "R20") (pin "2") (pinfunction "2_2") (pintype "passive"))
      (node (ref "R21") (pin "2") (pinfunction "2_2") (pintype "passive"))
      (node (ref "R22") (pin "2") (pinfunction "2_2") (pintype "passive"))
      (node (ref "R23") (pin "2") (pinfunction "2_2") (pintype "passive"))
      (node (ref "R24") (pin "2") (pinfunction "2_2") (pintype "passive"))
      (node (ref "R25") (pin "2") (pinfunction "2_2") (pintype "passive"))
      (node (ref "R26") (pin "2") (pinfunction "2_2") (pintype "passive"))
      (node (ref "R27") (pin "2") (pinfunction "2_2") (pintype "passive"))
      (node (ref "R3") (pin "2") (pinfunction "2_2") (pintype "passive"))
      (node (ref "R30") (pin "2") (pinfunction "2_2") (pintype "passive"))
      (node (ref "R31") (pin "2") (pinfunction "2_2") (pintype "passive"))
      (node (ref "R4") (pin "2") (pinfunction "2_2") (pintype "passive"))
      (node (ref "R5") (pin "2") (pinfunction "2_2") (pintype "passive"))
      (node (ref "R6") (pin "2") (pinfunction "2_2") (pintype "passive"))
      (node (ref "R7") (pin "2") (pinfunction "2_2") (pintype "passive"))
      (node (ref "R8") (pin "2") (pinfunction "2_2") (pintype "passive"))
      (node (ref "R9") (pin "2") (pinfunction "2_2") (pintype "passive"))
      (node (ref "U1") (pin "14") (pinfunction "VCC_14") (pintype "bidirectional"))
      (node (ref "U1") (pin "2") (pinfunction "UVCC_2") (pintype "bidirectional"))
      (node (ref "U1") (pin "24") (pinfunction "AVCC_24") (pintype "bidirectional"))
      (node (ref "U1") (pin "34") (pinfunction "VCC_34") (pintype "bidirectional"))
      (node (ref "U1") (pin "44") (pinfunction "AVCC_44") (pintype "bidirectional"))
      (node (ref "U1") (pin "7") (pinfunction "VBUS_7") (pintype "bidirectional"))
      (node (ref "U3") (pin "1") (pinfunction "VIN_1") (pintype "input"))
      (node (ref "U3") (pin "3") (pinfunction "EN_3") (pintype "input"))
    )
    (net (code "49") (name "unconnected-(CN1-PadID)") (class "Default")
      (node (ref "CN1") (pin "ID") (pinfunction "ID_ID") (pintype "bidirectional"))
    )
    (net (code "50") (name "unconnected-(U2-INT-Pad12)") (class "Default")
      (node (ref "U2") (pin "12") (pinfunction "INT_12") (pintype "output"))
    )
    (net (code "51") (name "unconnected-(U3-BYP-Pad4)") (class "Default")
      (node (ref "U3") (pin "4") (pinfunction "BYP_4") (pintype "passive"))
    )
    (net (code "52") (name "unconnected-(U4-OS-Pad3)") (class "Default")
      (node (ref "U4") (pin "3") (pinfunction "OS_3") (pintype "bidirectional"))
    )
  )
)
